# Arduino_Nano.net
KiCad netlist of a schematic drawn in Altium Designer
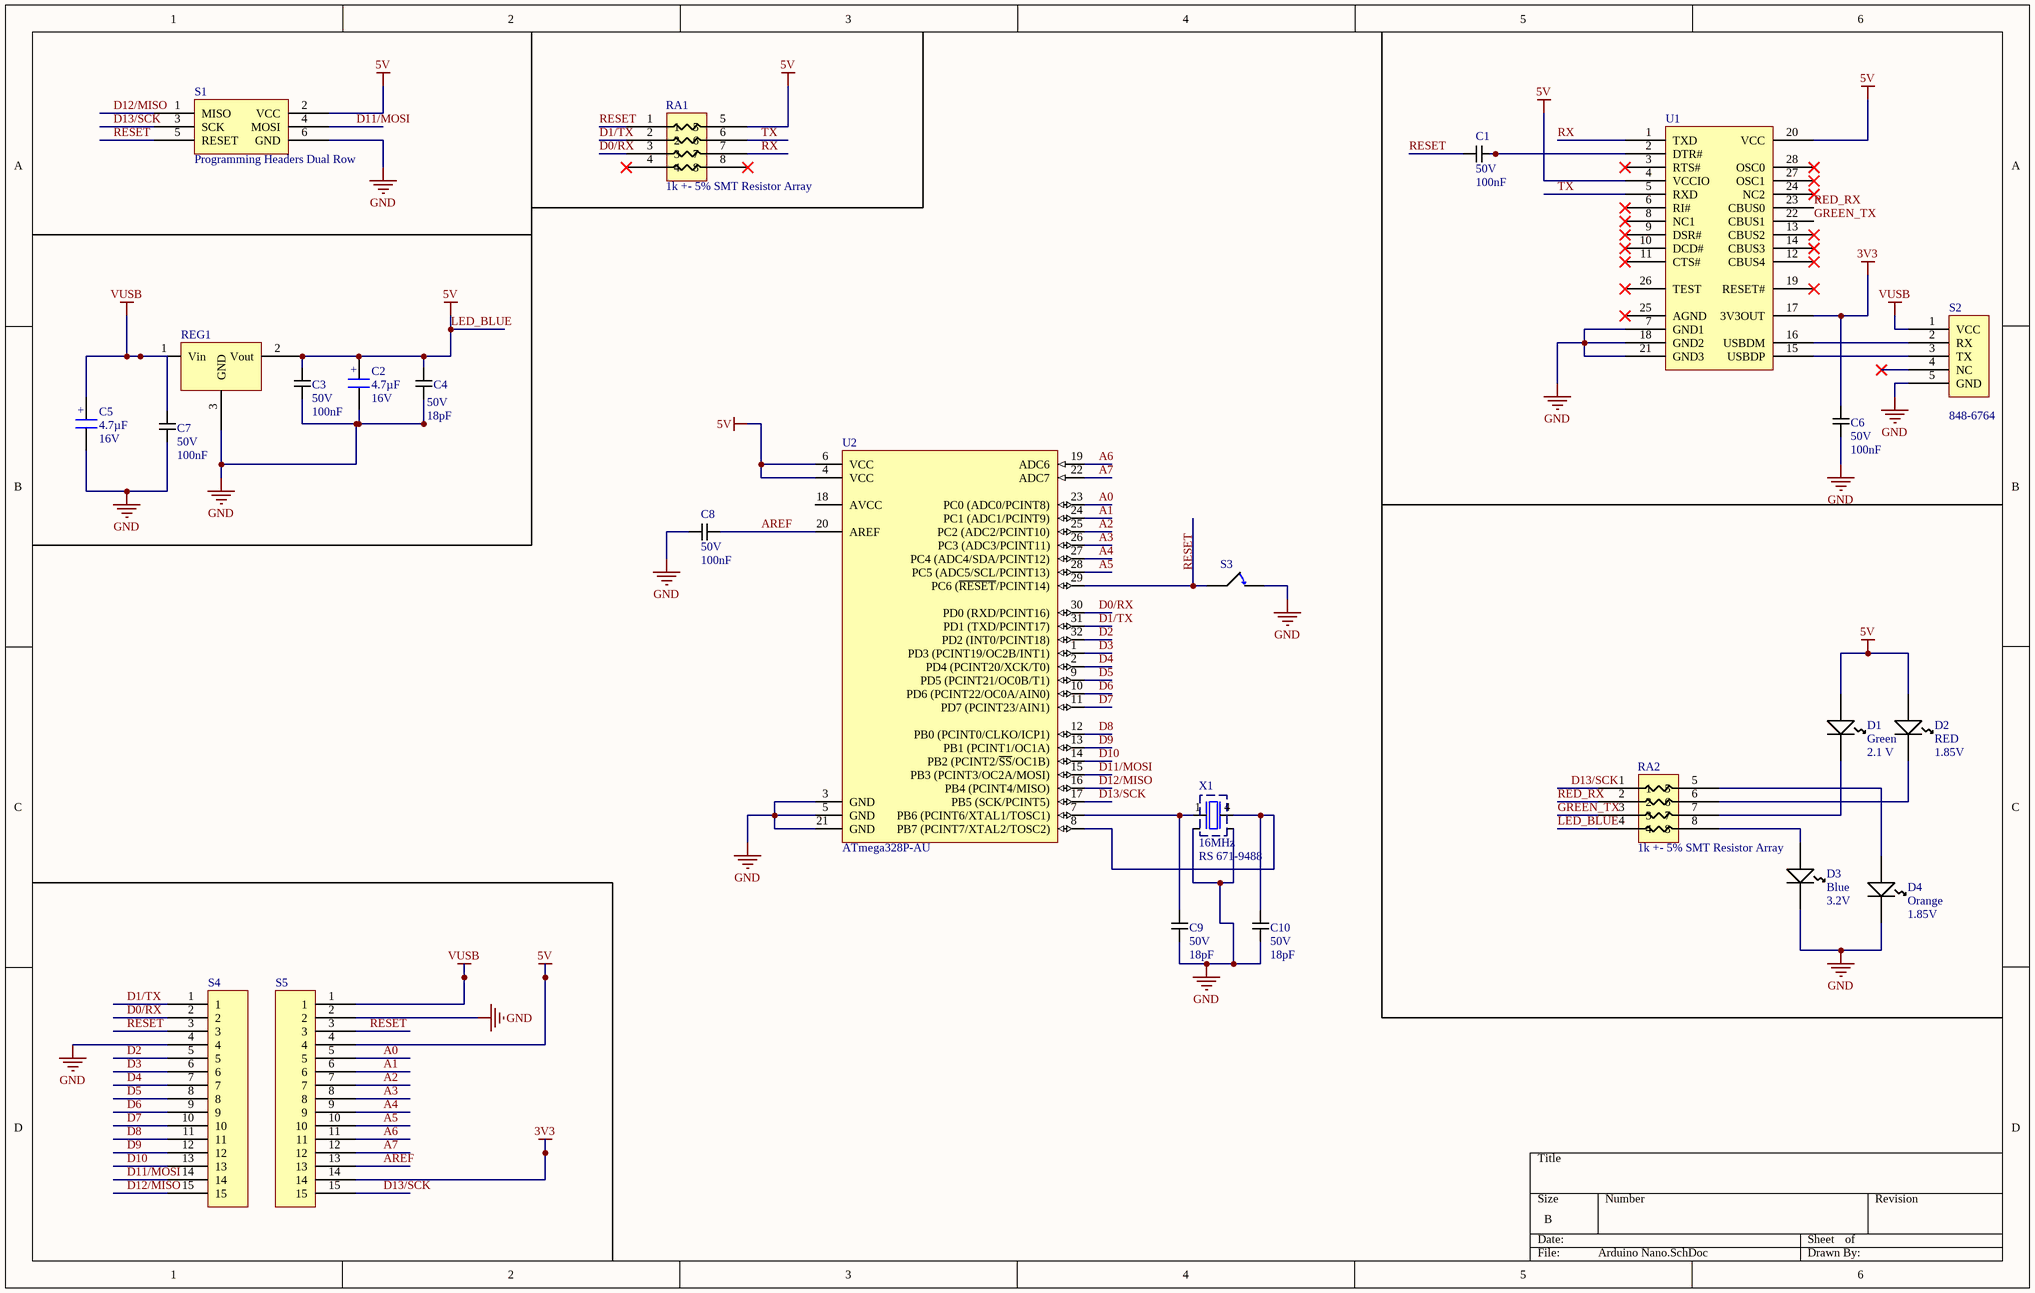
[diagram p0: Arduino Nano.SchDoc]

(export (version "E")
  (design (tool "Eeschema 10.0.6"))
  (components
    (comp (ref "C1")
      (value "100nF Ceramic Multilayer Capacitor_1")
      (footprint "CAPCP2012X09N")
      (description "AVX 0805 Standard 100nF Ceramic Multilayer Capacitor, 50 V dc X7R Dielectric ±10% SMD")
      (fields
        (field (name "MANUFACTURER") "AVX")
        (field (name "VOLTAGE") "50V")
        (field (name "CAPACITANCE") "100nF")
        (field (name "CREATOR") "Ritesh Kanjee")
      )
      (libsource (lib "RS Components - Capacitors") (part "100nF Ceramic Multilayer Capacitor_1"))
    )
    (comp (ref "C2")
      (value "4.7µF")
      (footprint "CASE A - 3216X18")
      (description "Capacitor,tantalum,SMT,16V,4.7uF,10%,A-case")
      (fields
        (field (name "TOLERANCE") "10%")
        (field (name "VOLTAGE") "16V")
        (field (name "Comment") "Capacitor SMT Tantalum")
        (field (name "PUBLISHER") "DPSS")
      )
      (libsource (lib "RS Components - Capacitors") (part "4.7µF Tant RS 496-3545"))
    )
    (comp (ref "C3")
      (value "100nF Ceramic Multilayer Capacitor_1")
      (footprint "CAPCP2012X09N")
      (description "AVX 0805 Standard 100nF Ceramic Multilayer Capacitor, 50 V dc X7R Dielectric ±10% SMD")
      (fields
        (field (name "MANUFACTURER") "AVX")
        (field (name "VOLTAGE") "50V")
        (field (name "CAPACITANCE") "100nF")
        (field (name "CREATOR") "Ritesh Kanjee")
      )
      (libsource (lib "RS Components - Capacitors") (part "100nF Ceramic Multilayer Capacitor_1"))
    )
    (comp (ref "C4")
      (value "C0805C180J5GACTU")
      (footprint "CAPCP2012X09N")
      (description "18pF Ceramic Multilayer Capacitor, 50 V dc C0G Dielectric ±5% SMD")
      (fields
        (field (name "MANUFACTURER") "Kemet")
        (field (name "VOLTAGE") "50V")
        (field (name "CAPACITANCE") "18pF")
        (field (name "CREATOR") "Ritesh Kanjee")
      )
      (libsource (lib "RS Components - Capacitors") (part "18pF Ceramic Multilayer Capacitor, 50 V dc C0G Dielectric ±5% SMD"))
    )
    (comp (ref "C5")
      (value "4.7µF")
      (footprint "CASE A - 3216X18")
      (description "Capacitor,tantalum,SMT,16V,4.7uF,10%,A-case")
      (fields
        (field (name "TOLERANCE") "10%")
        (field (name "VOLTAGE") "16V")
        (field (name "Comment") "Capacitor SMT Tantalum")
        (field (name "PUBLISHER") "DPSS")
      )
      (libsource (lib "RS Components - Capacitors") (part "4.7µF Tant RS 496-3545"))
    )
    (comp (ref "C6")
      (value "100nF Ceramic Multilayer Capacitor_1")
      (footprint "CAPCP2012X09N")
      (description "AVX 0805 Standard 100nF Ceramic Multilayer Capacitor, 50 V dc X7R Dielectric ±10% SMD")
      (fields
        (field (name "MANUFACTURER") "AVX")
        (field (name "VOLTAGE") "50V")
        (field (name "CAPACITANCE") "100nF")
        (field (name "CREATOR") "Ritesh Kanjee")
      )
      (libsource (lib "RS Components - Capacitors") (part "100nF Ceramic Multilayer Capacitor_1"))
    )
    (comp (ref "C7")
      (value "100nF Ceramic Multilayer Capacitor_1")
      (footprint "CAPCP2012X09N")
      (description "AVX 0805 Standard 100nF Ceramic Multilayer Capacitor, 50 V dc X7R Dielectric ±10% SMD")
      (fields
        (field (name "MANUFACTURER") "AVX")
        (field (name "VOLTAGE") "50V")
        (field (name "CAPACITANCE") "100nF")
        (field (name "CREATOR") "Ritesh Kanjee")
      )
      (libsource (lib "RS Components - Capacitors") (part "100nF Ceramic Multilayer Capacitor_1"))
    )
    (comp (ref "C8")
      (value "100nF Ceramic Multilayer Capacitor_1")
      (footprint "CAPCP2012X09N")
      (description "AVX 0805 Standard 100nF Ceramic Multilayer Capacitor, 50 V dc X7R Dielectric ±10% SMD")
      (fields
        (field (name "MANUFACTURER") "AVX")
        (field (name "VOLTAGE") "50V")
        (field (name "CAPACITANCE") "100nF")
        (field (name "CREATOR") "Ritesh Kanjee")
      )
      (libsource (lib "RS Components - Capacitors") (part "100nF Ceramic Multilayer Capacitor_1"))
    )
    (comp (ref "C9")
      (value "C0805C180J5GACTU")
      (footprint "CAPCP2012X09N")
      (description "18pF Ceramic Multilayer Capacitor, 50 V dc C0G Dielectric ±5% SMD")
      (fields
        (field (name "MANUFACTURER") "Kemet")
        (field (name "VOLTAGE") "50V")
        (field (name "CAPACITANCE") "18pF")
        (field (name "CREATOR") "Ritesh Kanjee")
      )
      (libsource (lib "RS Components - Capacitors") (part "18pF Ceramic Multilayer Capacitor, 50 V dc C0G Dielectric ±5% SMD"))
    )
    (comp (ref "C10")
      (value "C0805C180J5GACTU")
      (footprint "CAPCP2012X09N")
      (description "18pF Ceramic Multilayer Capacitor, 50 V dc C0G Dielectric ±5% SMD")
      (fields
        (field (name "MANUFACTURER") "Kemet")
        (field (name "VOLTAGE") "50V")
        (field (name "CAPACITANCE") "18pF")
        (field (name "CREATOR") "Ritesh Kanjee")
      )
      (libsource (lib "RS Components - Capacitors") (part "18pF Ceramic Multilayer Capacitor, 50 V dc C0G Dielectric ±5% SMD"))
    )
    (comp (ref "D1")
      (value "Kingbright Green LED, 70 mcd 120 ° 0805")
      (footprint "LED1913X12NGREEN")
      (fields
        (field (name "MANUFACTURER") "KingBright")
        (field (name "MANUFACTURER PART NO.") "KP-2012MGC")
        (field (name "COLOR") "Green")
        (field (name "FORWARD VOLTAGE") "2.1 V")
        (field (name "CREATOR") "Ritesh Kanjee")
      )
      (libsource (lib "KingBright LEDs") (part "Kingbright Green LED, 70 mcd 120 ° 0805"))
    )
    (comp (ref "D2")
      (value "Kingbright Red LED, 100 mcd 120 ° 0805")
      (footprint "LED1913X12NRED")
      (fields
        (field (name "MANUFACTURER") "KingBright")
        (field (name "MANUFACTURER PART NO.") "KP-2012SRC-PRV")
        (field (name "COLOR") "RED")
        (field (name "FORWARD VOLTAGE") "1.85V")
        (field (name "CREATOR") "Ritesh Kanjee")
      )
      (libsource (lib "KingBright LEDs") (part "Kingbright Red LED, 100 mcd 120 ° 0805"))
    )
    (comp (ref "D3")
      (value "Kingbright Blue LED, 60 mcd 120 ° 0805")
      (footprint "LED1913X12NBLUE")
      (fields
        (field (name "MANUFACTURER") "KingBright")
        (field (name "MANUFACTURER PART NO.") "KP-2012PBC-A")
        (field (name "COLOR") "Blue")
        (field (name "FORWARD VOLTAGE") "3.2V")
        (field (name "CREATOR") "Ritesh Kanjee")
      )
      (libsource (lib "KingBright LEDs") (part "Kingbright Blue LED, 60 mcd 120 ° 0805"))
    )
    (comp (ref "D4")
      (value "Kingbright Orange LED, 200 mcd 120 ° 0805")
      (footprint "LED1913X12NYEL/ORANGE")
      (fields
        (field (name "MANUFACTURER") "KingBright")
        (field (name "MANUFACTURER PART NO.") "KP-2012SEC")
        (field (name "COLOR") "Orange")
        (field (name "FORWARD VOLTAGE") "1.85V")
        (field (name "CREATOR") "Ritesh Kanjee")
      )
      (libsource (lib "KingBright LEDs") (part "Kingbright Orange LED, 200 mcd 120 ° 0805"))
    )
    (comp (ref "RA1")
      (value "1k +- 5% SMT Resistor Array")
      (footprint "1206 RA")
      (description "1k +- 5% SMT Resistor Array 4 Res")
      (fields
        (field (name "MANUFACTURER") "Bourns")
        (field (name "MANUFACTURER PART NO.") "CAY16-102J4LF")
        (field (name "CREATOR") "R Kanjee")
      )
      (libsource (lib "Bourns  Resistor Arrays") (part "1k +- 5% SMT Resistor Array"))
    )
    (comp (ref "RA2")
      (value "1k +- 5% SMT Resistor Array")
      (footprint "1206 RA")
      (description "1k +- 5% SMT Resistor Array 4 Res")
      (fields
        (field (name "MANUFACTURER") "Bourns")
        (field (name "MANUFACTURER PART NO.") "CAY16-102J4LF")
        (field (name "CREATOR") "R Kanjee")
      )
      (libsource (lib "Bourns  Resistor Arrays") (part "1k +- 5% SMT Resistor Array"))
    )
    (comp (ref "REG1")
      (value "LM1117MP-5.0/NOPB, Low Dropout Voltage Regulator, 1.5A, 5 V ±1%, 4-Pin SOT-223")
      (footprint "SOT230P700X180-4N")
      (fields (field (name "MANUFACTURER") "Texas Instruments") (field (name "CREATED BY") "R Kanjee"))
      (libsource (lib "TI Low Dropout Voltage Regulator") (part "LM1117MP-5.0"))
    )
    (comp (ref "S1")
      (value "Programming Headers Dual Row")
      (footprint "ISP HEADER")
      (fields
        (field (name "MANUFACTURER") "FCI")
        (field (name "MANUFACTURER PART NO.") "68000-236HLF")
        (field (name "CREATED BY") "R Kanjee")
      )
      (libsource (lib "PCB Headers") (part "Programming ISP, Programming Headers Dual Row"))
    )
    (comp (ref "S2")
      (value "NewMolex Right Angle SMT Female Type B Micro USB Connector, 30 V ac, 1.8A")
      (footprint "MicroUSB")
      (fields
        (field (name "MANUFACTURER") "Molex")
        (field (name "MANUFACTURER PART NO.") "105017-0001")
        (field (name "RS STOCK NO") "848-6764")
        (field (name "CREATOR") "R Kanjee")
      )
      (libsource (lib "Molex Connectors") (part "Micro USB Connector, 30 V ac, 1.8A"))
    )
    (comp (ref "S3")
      (value "Button Tactile Switch, NO 0.05 A 0.8mm")
      (footprint "Button8014X17N")
      (fields
        (field (name "MANUFACTURER") "C & K")
        (field (name "MANUFACTURER PART NO.") "B3F1000")
        (field (name "CREATOR") "R Kanjee")
      )
      (libsource (lib "Omron Tactile Switches") (part "Button Tactile Switch, NO 0.05 A 0.8mm"))
    )
    (comp (ref "S4")
      (value "connector;str header;single row;.1 cont centers;.095 tail;gold or gtx;36 contact")
      (footprint "Header")
      (fields
        (field (name "MANUFACTURER") "FCI")
        (field (name "MANUFACTURER PART NO.") "68000-236HLF")
        (field (name "CREATED BY") "R Kanjee")
      )
      (libsource (lib "") (part "Single row; PCB headers_1"))
    )
    (comp (ref "S5")
      (value "connector;str header;single row;.1 cont centers;.095 tail;gold or gtx;36 contact")
      (footprint "Header")
      (fields
        (field (name "MANUFACTURER") "FCI")
        (field (name "MANUFACTURER PART NO.") "68000-236HLF")
        (field (name "CREATED BY") "R Kanjee")
      )
      (libsource (lib "PCB Headers") (part "Single row; PCB headers"))
    )
    (comp (ref "U1")
      (value "FT232RL, Universal Asynchronous Receiver & Transmitter 3MBd, 28-Pin, SSOP")
      (footprint "SOP65P780X200-28N")
      (fields
        (field (name "MANUFACTURER PART NO.") "FT232RL")
        (field (name "MANUFACTURER") "FTDI Chip")
        (field (name "CREATOR") "R Kanjee")
      )
      (libsource (lib "FTDI RS232toUSB") (part "FT232RL USB to UART, Universal Asynchronous Receiver & Transmitter 3MBd, 28-Pin, SSOP"))
    )
    (comp (ref "U2")
      (value "ATmega328P-AU")
      (footprint "32A_M")
      (libsource (lib "Altium Content Vault") (part "MC-8B-ATM48-SQ32"))
    )
    (comp (ref "X1")
      (value "16MHz")
      (footprint "Aker S5C Crystal")
      (description "Aker S5C SMT Crystal")
      (fields
        (field (name "MANUFACTURER") "Aker")
        (field (name "MANUFACTURER PART #") "C5S-16.000-12-3030-X")
        (field (name "RS") "RS 671-9488")
        (field (name "CREATOR") "R Kanjee")
      )
      (libsource (lib "Aker Crystals") (part "Aker  C5S-16.000-12-3030-X"))
    )
  )
  (nets
    (net (code "1") (name "/A0") (class "Default")
      (node (ref "S5") (pin "5") (pinfunction "5_5") (pintype "passive"))
      (node (ref "U2") (pin "23") (pinfunction "PC0_(ADC0/PCINT8)_23") (pintype "bidirectional"))
    )
    (net (code "2") (name "/A1") (class "Default")
      (node (ref "S5") (pin "6") (pinfunction "6_6") (pintype "passive"))
      (node (ref "U2") (pin "24") (pinfunction "PC1_(ADC1/PCINT9)_24") (pintype "bidirectional"))
    )
    (net (code "3") (name "/A2") (class "Default")
      (node (ref "S5") (pin "7") (pinfunction "7_7") (pintype "passive"))
      (node (ref "U2") (pin "25") (pinfunction "PC2_(ADC2/PCINT10)_25") (pintype "bidirectional"))
    )
    (net (code "4") (name "/A3") (class "Default")
      (node (ref "S5") (pin "8") (pinfunction "8_8") (pintype "passive"))
      (node (ref "U2") (pin "26") (pinfunction "PC3_(ADC3/PCINT11)_26") (pintype "bidirectional"))
    )
    (net (code "5") (name "/A4") (class "Default")
      (node (ref "S5") (pin "9") (pinfunction "9_9") (pintype "passive"))
      (node (ref "U2") (pin "27") (pinfunction "PC4_(ADC4/SDA/PCINT12)_27") (pintype "bidirectional"))
    )
    (net (code "6") (name "/A5") (class "Default")
      (node (ref "S5") (pin "10") (pinfunction "10_10") (pintype "passive"))
      (node (ref "U2") (pin "28") (pinfunction "PC5_(ADC5/SCL/PCINT13)_28") (pintype "bidirectional"))
    )
    (net (code "7") (name "/A6") (class "Default")
      (node (ref "S5") (pin "11") (pinfunction "11_11") (pintype "passive"))
      (node (ref "U2") (pin "19") (pinfunction "ADC6_19") (pintype "input"))
    )
    (net (code "8") (name "/A7") (class "Default")
      (node (ref "S5") (pin "12") (pinfunction "12_12") (pintype "passive"))
      (node (ref "U2") (pin "22") (pinfunction "ADC7_22") (pintype "input"))
    )
    (net (code "9") (name "/AREF") (class "Default")
      (node (ref "C8") (pin "1") (pinfunction "1_1") (pintype "passive"))
      (node (ref "S5") (pin "13") (pinfunction "13_13") (pintype "passive"))
      (node (ref "U2") (pin "20") (pinfunction "AREF_20") (pintype "passive"))
    )
    (net (code "10") (name "/D0{slash}RX") (class "Default")
      (node (ref "RA1") (pin "3") (pinfunction "3_3") (pintype "passive"))
      (node (ref "S4") (pin "2") (pinfunction "2_2") (pintype "passive"))
      (node (ref "U2") (pin "30") (pinfunction "PD0_(RXD/PCINT16)_30") (pintype "bidirectional"))
    )
    (net (code "11") (name "/D1{slash}TX") (class "Default")
      (node (ref "RA1") (pin "2") (pinfunction "2_2") (pintype "passive"))
      (node (ref "S4") (pin "1") (pinfunction "1_1") (pintype "passive"))
      (node (ref "U2") (pin "31") (pinfunction "PD1_(TXD/PCINT17)_31") (pintype "bidirectional"))
    )
    (net (code "12") (name "/D2") (class "Default")
      (node (ref "S4") (pin "5") (pinfunction "5_5") (pintype "passive"))
      (node (ref "U2") (pin "32") (pinfunction "PD2_(INT0/PCINT18)_32") (pintype "bidirectional"))
    )
    (net (code "13") (name "/D3") (class "Default")
      (node (ref "S4") (pin "6") (pinfunction "6_6") (pintype "passive"))
      (node (ref "U2") (pin "1") (pinfunction "PD3_(PCINT19/OC2B/INT1)_1") (pintype "bidirectional"))
    )
    (net (code "14") (name "/D4") (class "Default")
      (node (ref "S4") (pin "7") (pinfunction "7_7") (pintype "passive"))
      (node (ref "U2") (pin "2") (pinfunction "PD4_(PCINT20/XCK/T0)_2") (pintype "bidirectional"))
    )
    (net (code "15") (name "/D5") (class "Default")
      (node (ref "S4") (pin "8") (pinfunction "8_8") (pintype "passive"))
      (node (ref "U2") (pin "9") (pinfunction "PD5_(PCINT21/OC0B/T1)_9") (pintype "bidirectional"))
    )
    (net (code "16") (name "/D6") (class "Default")
      (node (ref "S4") (pin "9") (pinfunction "9_9") (pintype "passive"))
      (node (ref "U2") (pin "10") (pinfunction "PD6_(PCINT22/OC0A/AIN0)_10") (pintype "bidirectional"))
    )
    (net (code "17") (name "/D7") (class "Default")
      (node (ref "S4") (pin "10") (pinfunction "10_10") (pintype "passive"))
      (node (ref "U2") (pin "11") (pinfunction "PD7_(PCINT23/AIN1)_11") (pintype "bidirectional"))
    )
    (net (code "18") (name "/D8") (class "Default")
      (node (ref "S4") (pin "11") (pinfunction "11_11") (pintype "passive"))
      (node (ref "U2") (pin "12") (pinfunction "PB0_(PCINT0/CLKO/ICP1)_12") (pintype "bidirectional"))
    )
    (net (code "19") (name "/D9") (class "Default")
      (node (ref "S4") (pin "12") (pinfunction "12_12") (pintype "passive"))
      (node (ref "U2") (pin "13") (pinfunction "PB1_(PCINT1/OC1A)_13") (pintype "bidirectional"))
    )
    (net (code "20") (name "/D10") (class "Default")
      (node (ref "S4") (pin "13") (pinfunction "13_13") (pintype "passive"))
      (node (ref "U2") (pin "14") (pinfunction "PB2_(PCINT2/~{SS}/OC1B)_14") (pintype "bidirectional"))
    )
    (net (code "21") (name "/D11{slash}MOSI") (class "Default")
      (node (ref "S1") (pin "4") (pinfunction "MOSI_4") (pintype "passive"))
      (node (ref "S4") (pin "14") (pinfunction "14_14") (pintype "passive"))
      (node (ref "U2") (pin "15") (pinfunction "PB3_(PCINT3/OC2A/MOSI)_15") (pintype "bidirectional"))
    )
    (net (code "22") (name "/D12{slash}MISO") (class "Default")
      (node (ref "S1") (pin "1") (pinfunction "MISO_1") (pintype "passive"))
      (node (ref "S4") (pin "15") (pinfunction "15_15") (pintype "passive"))
      (node (ref "U2") (pin "16") (pinfunction "PB4_(PCINT4/MISO)_16") (pintype "bidirectional"))
    )
    (net (code "23") (name "/D13{slash}SCK") (class "Default")
      (node (ref "RA2") (pin "1") (pinfunction "1_1") (pintype "passive"))
      (node (ref "S1") (pin "3") (pinfunction "SCK_3") (pintype "passive"))
      (node (ref "S5") (pin "15") (pinfunction "15_15") (pintype "passive"))
      (node (ref "U2") (pin "17") (pinfunction "PB5_(SCK/PCINT5)_17") (pintype "bidirectional"))
    )
    (net (code "24") (name "/GREEN_TX") (class "Default")
      (node (ref "RA2") (pin "3") (pinfunction "3_3") (pintype "passive"))
      (node (ref "U1") (pin "22") (pinfunction "CBUS1_22") (pintype "passive"))
    )
    (net (code "25") (name "/RED_RX") (class "Default")
      (node (ref "RA2") (pin "2") (pinfunction "2_2") (pintype "passive"))
      (node (ref "U1") (pin "23") (pinfunction "CBUS0_23") (pintype "passive"))
    )
    (net (code "26") (name "/RESET") (class "Default")
      (node (ref "C1") (pin "1") (pinfunction "1_1") (pintype "passive"))
      (node (ref "RA1") (pin "1") (pinfunction "1_1") (pintype "passive"))
      (node (ref "S1") (pin "5") (pinfunction "RESET_5") (pintype "passive"))
      (node (ref "S4") (pin "3") (pinfunction "3_3") (pintype "passive"))
      (node (ref "S5") (pin "3") (pinfunction "3_3") (pintype "passive"))
    )
    (net (code "27") (name "/RX") (class "Default")
      (node (ref "RA1") (pin "7") (pinfunction "7_7") (pintype "passive"))
      (node (ref "U1") (pin "1") (pinfunction "TXD_1") (pintype "passive"))
    )
    (net (code "28") (name "/TX") (class "Default")
      (node (ref "RA1") (pin "6") (pinfunction "6_6") (pintype "passive"))
      (node (ref "U1") (pin "5") (pinfunction "RXD_5") (pintype "passive"))
    )
    (net (code "29") (name "3V3") (class "Default")
      (node (ref "C6") (pin "2") (pinfunction "2_2") (pintype "passive"))
      (node (ref "S5") (pin "14") (pinfunction "14_14") (pintype "passive"))
      (node (ref "U1") (pin "17") (pinfunction "3V3OUT_17") (pintype "passive"))
    )
    (net (code "30") (name "5V") (class "Default")
      (node (ref "C2") (pin "1") (pinfunction "1_1") (pintype "passive"))
      (node (ref "C3") (pin "2") (pinfunction "2_2") (pintype "passive"))
      (node (ref "C4") (pin "2") (pinfunction "2_2") (pintype "passive"))
      (node (ref "D1") (pin "1") (pinfunction "A_1") (pintype "passive"))
      (node (ref "D2") (pin "1") (pinfunction "A_1") (pintype "passive"))
      (node (ref "RA1") (pin "5") (pinfunction "5_5") (pintype "passive"))
      (node (ref "RA2") (pin "4") (pinfunction "4_4") (pintype "passive"))
      (node (ref "REG1") (pin "2") (pinfunction "Vout_2") (pintype "passive"))
      (node (ref "S1") (pin "2") (pinfunction "VCC_2") (pintype "passive"))
      (node (ref "S5") (pin "4") (pinfunction "4_4") (pintype "passive"))
      (node (ref "U1") (pin "20") (pinfunction "VCC_20") (pintype "passive"))
      (node (ref "U1") (pin "4") (pinfunction "VCCIO_4") (pintype "passive"))
      (node (ref "U2") (pin "4") (pinfunction "VCC_4") (pintype "power_in"))
      (node (ref "U2") (pin "6") (pinfunction "VCC_6") (pintype "power_in"))
    )
    (net (code "31") (name "GND") (class "Default")
      (node (ref "C10") (pin "1") (pinfunction "1_1") (pintype "passive"))
      (node (ref "C2") (pin "2") (pinfunction "2_2") (pintype "passive"))
      (node (ref "C3") (pin "1") (pinfunction "1_1") (pintype "passive"))
      (node (ref "C4") (pin "1") (pinfunction "1_1") (pintype "passive"))
      (node (ref "C5") (pin "2") (pinfunction "2_2") (pintype "passive"))
      (node (ref "C6") (pin "1") (pinfunction "1_1") (pintype "passive"))
      (node (ref "C7") (pin "1") (pinfunction "1_1") (pintype "passive"))
      (node (ref "C8") (pin "2") (pinfunction "2_2") (pintype "passive"))
      (node (ref "C9") (pin "1") (pinfunction "1_1") (pintype "passive"))
      (node (ref "D3") (pin "2") (pinfunction "K_2") (pintype "passive"))
      (node (ref "D4") (pin "2") (pinfunction "K_2") (pintype "passive"))
      (node (ref "REG1") (pin "3") (pinfunction "GND_3") (pintype "passive"))
      (node (ref "S1") (pin "6") (pinfunction "GND_6") (pintype "passive"))
      (node (ref "S2") (pin "5") (pinfunction "GND_5") (pintype "passive"))
      (node (ref "S3") (pin "1") (pinfunction "1_1") (pintype "passive"))
      (node (ref "S4") (pin "4") (pinfunction "4_4") (pintype "passive"))
      (node (ref "S5") (pin "2") (pinfunction "2_2") (pintype "passive"))
      (node (ref "U1") (pin "18") (pinfunction "GND2_18") (pintype "passive"))
      (node (ref "U1") (pin "21") (pinfunction "GND3_21") (pintype "passive"))
      (node (ref "U1") (pin "7") (pinfunction "GND1_7") (pintype "passive"))
      (node (ref "U2") (pin "21") (pinfunction "GND_21") (pintype "power_in"))
      (node (ref "U2") (pin "3") (pinfunction "GND_3") (pintype "power_in"))
      (node (ref "U2") (pin "5") (pinfunction "GND_5") (pintype "power_in"))
      (node (ref "X1") (pin "2") (pinfunction "Gnd_2") (pintype "power_in"))
      (node (ref "X1") (pin "3") (pinfunction "Gnd_3") (pintype "power_in"))
    )
    (net (code "32") (name "Net-(D1-K)") (class "Default")
      (node (ref "D1") (pin "2") (pinfunction "K_2") (pintype "passive"))
      (node (ref "RA2") (pin "7") (pinfunction "7_7") (pintype "passive"))
    )
    (net (code "33") (name "Net-(D2-K)") (class "Default")
      (node (ref "D2") (pin "2") (pinfunction "K_2") (pintype "passive"))
      (node (ref "RA2") (pin "6") (pinfunction "6_6") (pintype "passive"))
    )
    (net (code "34") (name "Net-(D3-A)") (class "Default")
      (node (ref "D3") (pin "1") (pinfunction "A_1") (pintype "passive"))
      (node (ref "RA2") (pin "8") (pinfunction "8_8") (pintype "passive"))
    )
    (net (code "35") (name "Net-(D4-A)") (class "Default")
      (node (ref "D4") (pin "1") (pinfunction "A_1") (pintype "passive"))
      (node (ref "RA2") (pin "5") (pinfunction "5_5") (pintype "passive"))
    )
    (net (code "36") (name "Net-(S2-RX)") (class "Default")
      (node (ref "S2") (pin "2") (pinfunction "RX_2") (pintype "passive"))
      (node (ref "U1") (pin "16") (pinfunction "USBDM_16") (pintype "passive"))
    )
    (net (code "37") (name "Net-(S2-TX)") (class "Default")
      (node (ref "S2") (pin "3") (pinfunction "TX_3") (pintype "passive"))
      (node (ref "U1") (pin "15") (pinfunction "USBDP_15") (pintype "passive"))
    )
    (net (code "38") (name "Net-(U1-DTR#)") (class "Default")
      (node (ref "C1") (pin "2") (pinfunction "2_2") (pintype "passive"))
      (node (ref "U1") (pin "2") (pinfunction "DTR#_2") (pintype "passive"))
    )
    (net (code "39") (name "Net-(U2-PB6_(PCINT6{slash}XTAL1{slash}TOSC1))") (class "Default")
      (node (ref "C9") (pin "2") (pinfunction "2_2") (pintype "passive"))
      (node (ref "U2") (pin "7") (pinfunction "PB6_(PCINT6/XTAL1/TOSC1)_7") (pintype "bidirectional"))
      (node (ref "X1") (pin "1") (pinfunction "1_1") (pintype "passive"))
    )
    (net (code "40") (name "Net-(U2-PB7_(PCINT7{slash}XTAL2{slash}TOSC2))") (class "Default")
      (node (ref "C10") (pin "2") (pinfunction "2_2") (pintype "passive"))
      (node (ref "U2") (pin "8") (pinfunction "PB7_(PCINT7/XTAL2/TOSC2)_8") (pintype "bidirectional"))
      (node (ref "X1") (pin "4") (pinfunction "4_4") (pintype "passive"))
    )
    (net (code "41") (name "Net-(U2-PC6_(~{RESET}{slash}PCINT14))") (class "Default")
      (node (ref "S3") (pin "1") (pinfunction "1_1") (pintype "passive"))
      (node (ref "U2") (pin "29") (pinfunction "PC6_(~{RESET}/PCINT14)_29") (pintype "bidirectional"))
    )
    (net (code "42") (name "VUSB") (class "Default")
      (node (ref "C5") (pin "1") (pinfunction "1_1") (pintype "passive"))
      (node (ref "C7") (pin "2") (pinfunction "2_2") (pintype "passive"))
      (node (ref "REG1") (pin "1") (pinfunction "Vin_1") (pintype "passive"))
      (node (ref "S2") (pin "1") (pinfunction "VCC_1") (pintype "passive"))
      (node (ref "S5") (pin "1") (pinfunction "1_1") (pintype "passive"))
    )
    (net (code "43") (name "unconnected-(RA1-Pad4)") (class "Default")
      (node (ref "RA1") (pin "4") (pinfunction "4_4") (pintype "passive+no_connect"))
    )
    (net (code "44") (name "unconnected-(RA1-Pad8)") (class "Default")
      (node (ref "RA1") (pin "8") (pinfunction "8_8") (pintype "passive+no_connect"))
    )
    (net (code "45") (name "unconnected-(S2-NC-Pad4)") (class "Default")
      (node (ref "S2") (pin "4") (pinfunction "NC_4") (pintype "passive+no_connect"))
    )
    (net (code "46") (name "unconnected-(U1-AGND-Pad25)") (class "Default")
      (node (ref "U1") (pin "25") (pinfunction "AGND_25") (pintype "passive+no_connect"))
    )
    (net (code "47") (name "unconnected-(U1-CBUS2-Pad13)") (class "Default")
      (node (ref "U1") (pin "13") (pinfunction "CBUS2_13") (pintype "passive+no_connect"))
    )
    (net (code "48") (name "unconnected-(U1-CBUS3-Pad14)") (class "Default")
      (node (ref "U1") (pin "14") (pinfunction "CBUS3_14") (pintype "passive+no_connect"))
    )
    (net (code "49") (name "unconnected-(U1-CBUS4-Pad12)") (class "Default")
      (node (ref "U1") (pin "12") (pinfunction "CBUS4_12") (pintype "passive+no_connect"))
    )
    (net (code "50") (name "unconnected-(U1-CTS#-Pad11)") (class "Default")
      (node (ref "U1") (pin "11") (pinfunction "CTS#_11") (pintype "passive+no_connect"))
    )
    (net (code "51") (name "unconnected-(U1-DCD#-Pad10)") (class "Default")
      (node (ref "U1") (pin "10") (pinfunction "DCD#_10") (pintype "passive+no_connect"))
    )
    (net (code "52") (name "unconnected-(U1-DSR#-Pad9)") (class "Default")
      (node (ref "U1") (pin "9") (pinfunction "DSR#_9") (pintype "passive+no_connect"))
    )
    (net (code "53") (name "unconnected-(U1-NC1-Pad8)") (class "Default")
      (node (ref "U1") (pin "8") (pinfunction "NC1_8") (pintype "passive+no_connect"))
    )
    (net (code "54") (name "unconnected-(U1-NC2-Pad24)") (class "Default")
      (node (ref "U1") (pin "24") (pinfunction "NC2_24") (pintype "passive+no_connect"))
    )
    (net (code "55") (name "unconnected-(U1-OSC0-Pad28)") (class "Default")
      (node (ref "U1") (pin "28") (pinfunction "OSC0_28") (pintype "passive+no_connect"))
    )
    (net (code "56") (name "unconnected-(U1-OSC1-Pad27)") (class "Default")
      (node (ref "U1") (pin "27") (pinfunction "OSC1_27") (pintype "passive+no_connect"))
    )
    (net (code "57") (name "unconnected-(U1-RESET#-Pad19)") (class "Default")
      (node (ref "U1") (pin "19") (pinfunction "RESET#_19") (pintype "passive+no_connect"))
    )
    (net (code "58") (name "unconnected-(U1-RI#-Pad6)") (class "Default")
      (node (ref "U1") (pin "6") (pinfunction "RI#_6") (pintype "passive+no_connect"))
    )
    (net (code "59") (name "unconnected-(U1-RTS#-Pad3)") (class "Default")
      (node (ref "U1") (pin "3") (pinfunction "RTS#_3") (pintype "passive+no_connect"))
    )
    (net (code "60") (name "unconnected-(U1-TEST-Pad26)") (class "Default")
      (node (ref "U1") (pin "26") (pinfunction "TEST_26") (pintype "passive+no_connect"))
    )
    (net (code "61") (name "unconnected-(U2-AVCC-Pad18)") (class "Default")
      (node (ref "U2") (pin "18") (pinfunction "AVCC_18") (pintype "power_in"))
    )
  )
)
